# 26PinSuperseal.net
KiCad netlist of a schematic drawn in Altium Designer
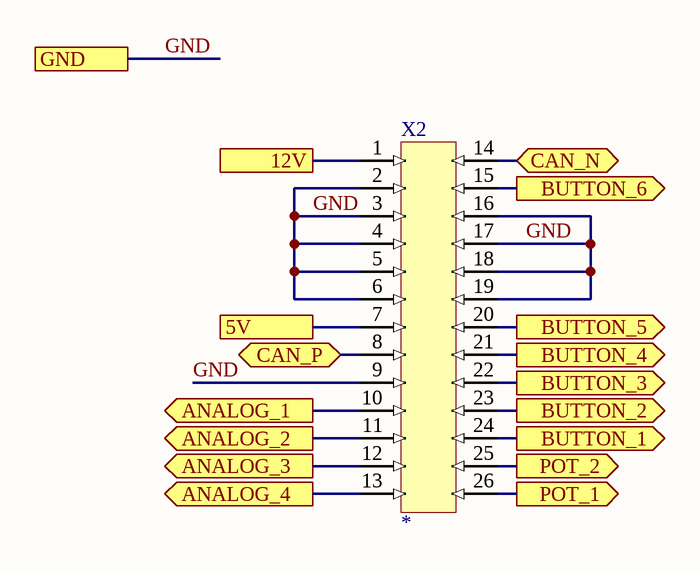
[diagram p0: 26PinSuperseal.SchDoc]

(export (version "E")
  (design (tool "Eeschema 10.0.6"))
  (components
    (comp (ref "X2")
      (value "*")
      (footprint "TE_Amp_6437288-6")
      (description "AMP SuperSeal Straight")
      (libsource (lib "altlib") (part "CONN 26POS"))
    )
  )
  (nets
    (net (code "1") (name "/5V") (class "Default") (node (ref "X2") (pin "7") (pintype "input")))
    (net (code "2") (name "/12V") (class "Default") (node (ref "X2") (pin "1") (pintype "input")))
    (net (code "3") (name "/ANALOG_1") (class "Default") (node (ref "X2") (pin "10") (pintype "input")))
    (net (code "4") (name "/ANALOG_2") (class "Default") (node (ref "X2") (pin "11") (pintype "input")))
    (net (code "5") (name "/ANALOG_3") (class "Default") (node (ref "X2") (pin "12") (pintype "input")))
    (net (code "6") (name "/ANALOG_4") (class "Default") (node (ref "X2") (pin "13") (pintype "input")))
    (net (code "7") (name "/BUTTON_1") (class "Default") (node (ref "X2") (pin "24") (pintype "input")))
    (net (code "8") (name "/BUTTON_2") (class "Default") (node (ref "X2") (pin "23") (pintype "input")))
    (net (code "9") (name "/BUTTON_3") (class "Default") (node (ref "X2") (pin "22") (pintype "input")))
    (net (code "10") (name "/BUTTON_4") (class "Default") (node (ref "X2") (pin "21") (pintype "input")))
    (net (code "11") (name "/BUTTON_5") (class "Default") (node (ref "X2") (pin "20") (pintype "input")))
    (net (code "12") (name "/BUTTON_6") (class "Default") (node (ref "X2") (pin "15") (pintype "input")))
    (net (code "13") (name "/CAN_N") (class "Default") (node (ref "X2") (pin "14") (pintype "input")))
    (net (code "14") (name "/CAN_P") (class "Default") (node (ref "X2") (pin "8") (pintype "input")))
    (net (code "15") (name "/GND") (class "Default")
      (node (ref "X2") (pin "16") (pintype "input"))
      (node (ref "X2") (pin "17") (pintype "input"))
      (node (ref "X2") (pin "18") (pintype "input"))
      (node (ref "X2") (pin "19") (pintype "input"))
      (node (ref "X2") (pin "2") (pintype "input"))
      (node (ref "X2") (pin "3") (pintype "input"))
      (node (ref "X2") (pin "4") (pintype "input"))
      (node (ref "X2") (pin "5") (pintype "input"))
      (node (ref "X2") (pin "6") (pintype "input"))
      (node (ref "X2") (pin "9") (pintype "input"))
    )
    (net (code "16") (name "/POT_1") (class "Default") (node (ref "X2") (pin "26") (pintype "input")))
    (net (code "17") (name "/POT_2") (class "Default") (node (ref "X2") (pin "25") (pintype "input")))
  )
)
